# SnapBIT-DUO.net
KiCad netlist of a schematic drawn in EAGLE
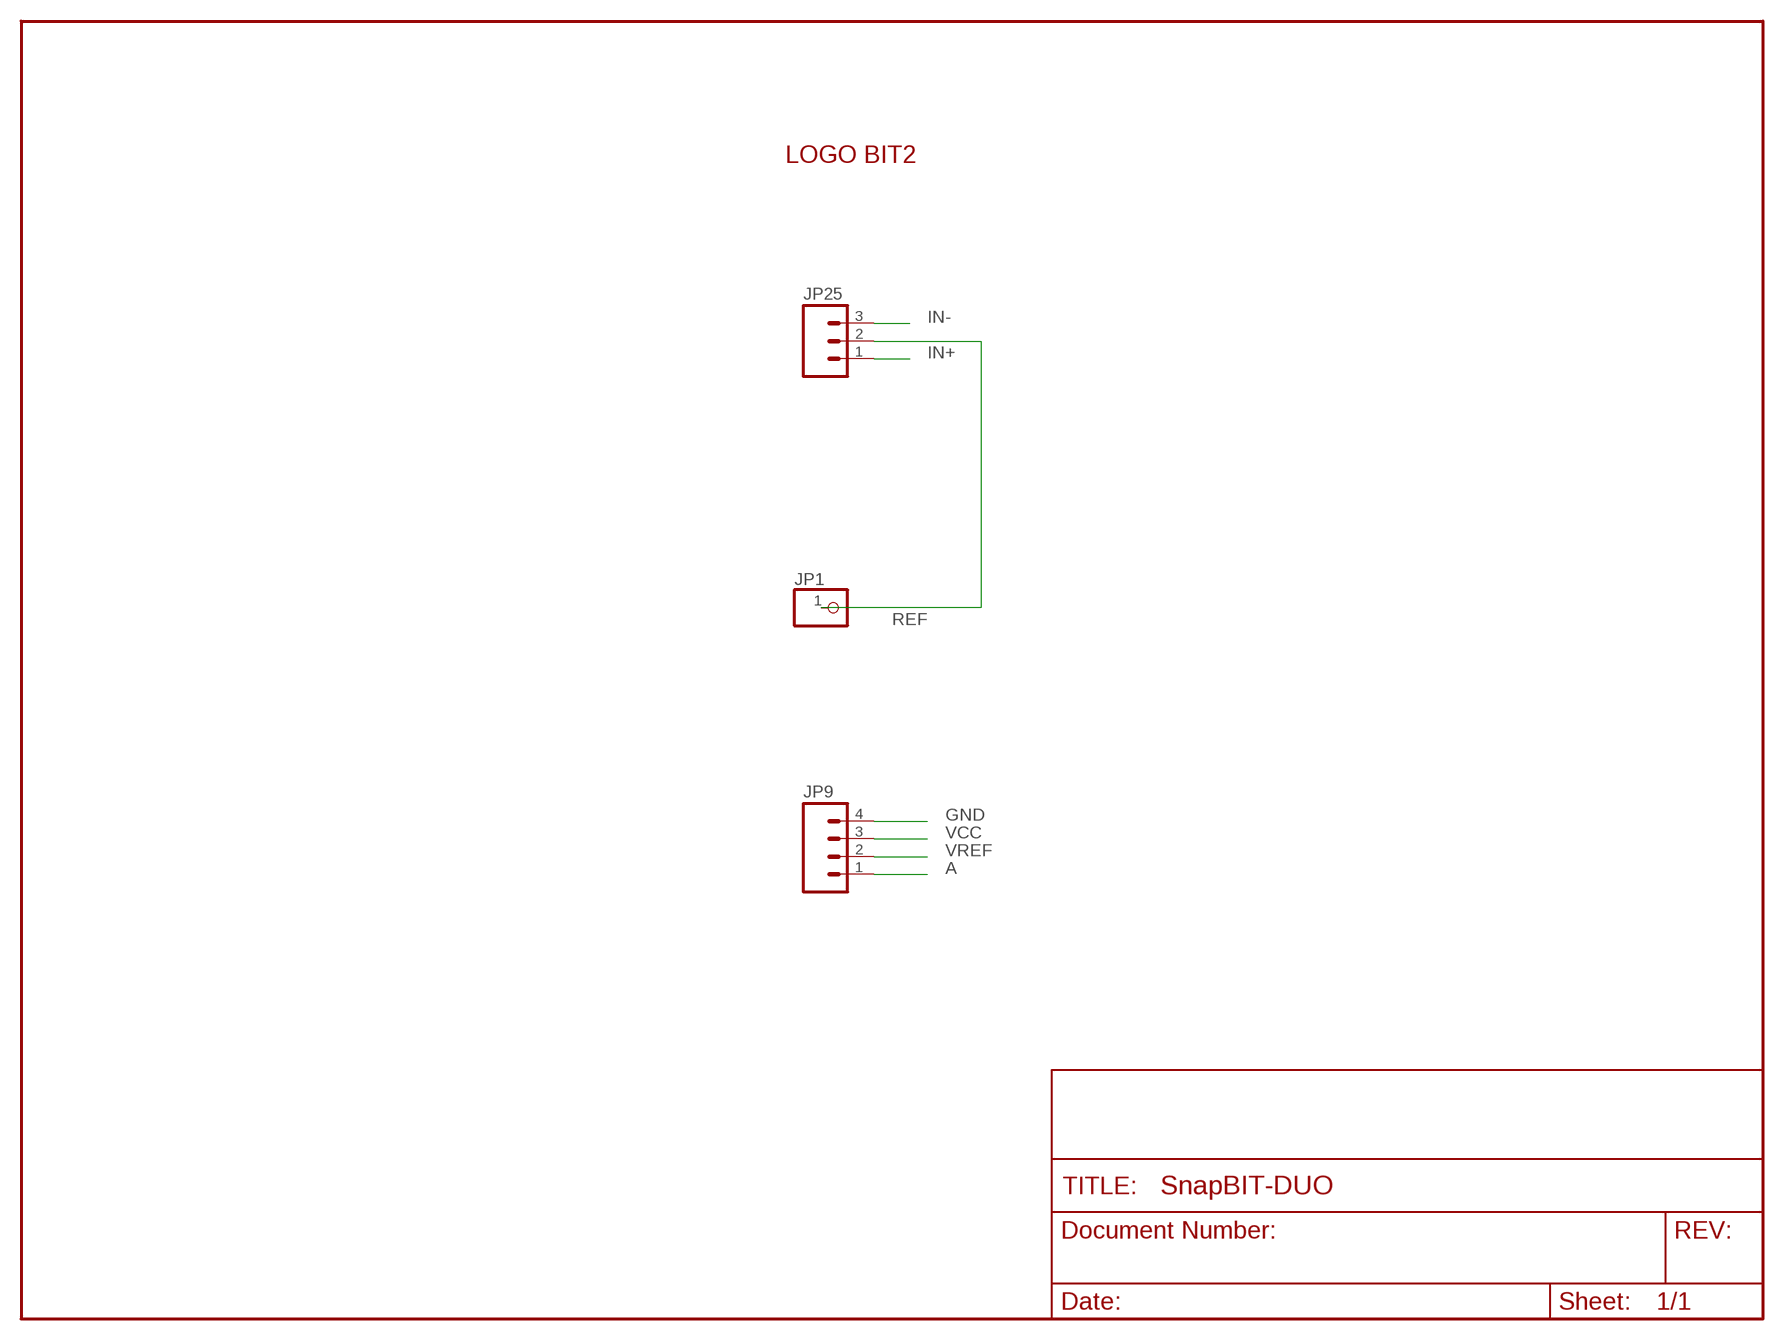
[diagram p0: schematic, sheet 1]

(export (version "E")
  (design (tool "Eeschema 10.0.6"))
  (components
    (comp (ref "JP1")
      (value "PINHD-1X1")
      (footprint "eagle-import:1X01")
      (libsource (lib "eagle-import") (part "PINHD-1X1"))
    )
    (comp (ref "JP9")
      (value "M04JST-PTH")
      (footprint "eagle-import:JST-4-PTH")
      (libsource (lib "eagle-import") (part "M04JST-PTH"))
    )
    (comp (ref "JP25")
      (value "M03JST-PTH")
      (footprint "eagle-import:JST-3-PTH")
      (libsource (lib "eagle-import") (part "M03JST-PTH"))
    )
    (comp (ref "U$1")
      (value "LOGO_BIT2(4.72X3.78)")
      (footprint "eagle-import:LOGO_BIT2")
      (libsource (lib "eagle-import") (part "LOGO_BIT2(4.72X3.78)"))
    )
  )
  (nets
    (net (code "1") (name "/A") (class "Default")
      (node (ref "JP9") (pin "1") (pinfunction "1_1") (pintype "passive"))
    )
    (net (code "2") (name "/GND") (class "Default")
      (node (ref "JP9") (pin "4") (pinfunction "4_4") (pintype "passive"))
    )
    (net (code "3") (name "/IN+") (class "Default")
      (node (ref "JP25") (pin "1") (pinfunction "1_1") (pintype "passive"))
    )
    (net (code "4") (name "/IN-") (class "Default")
      (node (ref "JP25") (pin "3") (pinfunction "3_3") (pintype "passive"))
    )
    (net (code "5") (name "/REF") (class "Default")
      (node (ref "JP1") (pin "1") (pinfunction "1_1") (pintype "passive"))
      (node (ref "JP25") (pin "2") (pinfunction "2_2") (pintype "passive"))
    )
    (net (code "6") (name "/VCC") (class "Default")
      (node (ref "JP9") (pin "3") (pinfunction "3_3") (pintype "passive"))
    )
    (net (code "7") (name "/VREF") (class "Default")
      (node (ref "JP9") (pin "2") (pinfunction "2_2") (pintype "passive"))
    )
  )
)
